# BatteryBoard.net
KiCad netlist of a schematic drawn in Altium Designer
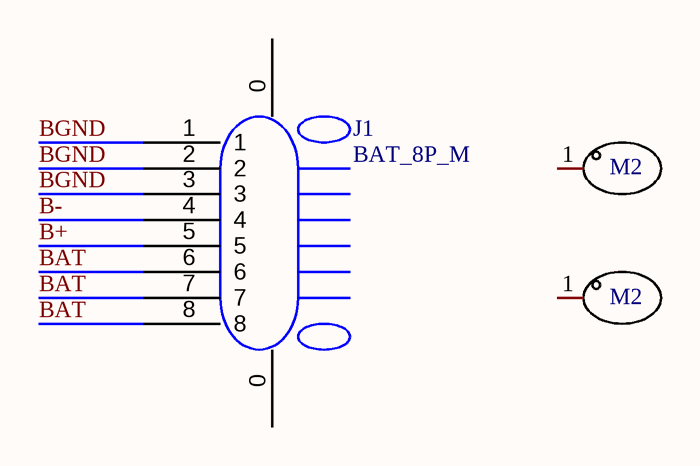
[diagram p0: BatteryBoard.SchDoc]

(export (version "E")
  (design (tool "Eeschema 10.0.6"))
  (components
    (comp (ref "J1") (value "BAT_8P_M") (footprint "BAT_8P_M") (libsource (lib "BAT") (part "BAT_8P_M")))
    (comp (ref "U1")
      (value "SMTSO2020CTJ")
      (footprint "M2*4*1.5+2.5*1")
      (fields (field (name "MANUFACTURER") "Sinhoo(雄和远景)"))
      (libsource (lib "NUT-SMD") (part "M2_NUT"))
    )
    (comp (ref "U2")
      (value "SMTSO2020CTJ")
      (footprint "M2*4*1.5+2.5*1")
      (fields (field (name "MANUFACTURER") "Sinhoo(雄和远景)"))
      (libsource (lib "NUT-SMD") (part "M2_NUT"))
    )
  )
  (nets
    (net (code "1") (name "/B+") (class "Default")
      (node (ref "J1") (pin "5") (pinfunction "5_5") (pintype "passive"))
    )
    (net (code "2") (name "/B-") (class "Default")
      (node (ref "J1") (pin "4") (pinfunction "4_4") (pintype "passive"))
    )
    (net (code "3") (name "/BAT") (class "Default")
      (node (ref "J1") (pin "6") (pinfunction "6_6") (pintype "passive"))
      (node (ref "J1") (pin "7") (pinfunction "7_7") (pintype "passive"))
      (node (ref "J1") (pin "8") (pinfunction "8_8") (pintype "passive"))
    )
    (net (code "4") (name "/BGND") (class "Default")
      (node (ref "J1") (pin "1") (pinfunction "1_1") (pintype "passive"))
      (node (ref "J1") (pin "2") (pinfunction "2_2") (pintype "passive"))
      (node (ref "J1") (pin "3") (pinfunction "3_3") (pintype "passive"))
    )
    (net (code "5") (name "unconnected-(J1-Pad0)") (class "Default")
      (node (ref "J1") (pin "0") (pinfunction "0_0") (pintype "passive"))
    )
    (net (code "6") (name "unconnected-(J1-Pad0)_1") (class "Default")
      (node (ref "J1") (pin "0") (pinfunction "0_0") (pintype "passive"))
    )
    (net (code "7") (name "unconnected-(U1-Pad1)") (class "Default")
      (node (ref "U1") (pin "1") (pinfunction "1_1") (pintype "passive"))
    )
    (net (code "8") (name "unconnected-(U2-Pad1)") (class "Default")
      (node (ref "U2") (pin "1") (pinfunction "1_1") (pintype "passive"))
    )
  )
)
